# 12_I2C_schdoc.net
KiCad netlist of a schematic drawn in Altium Designer
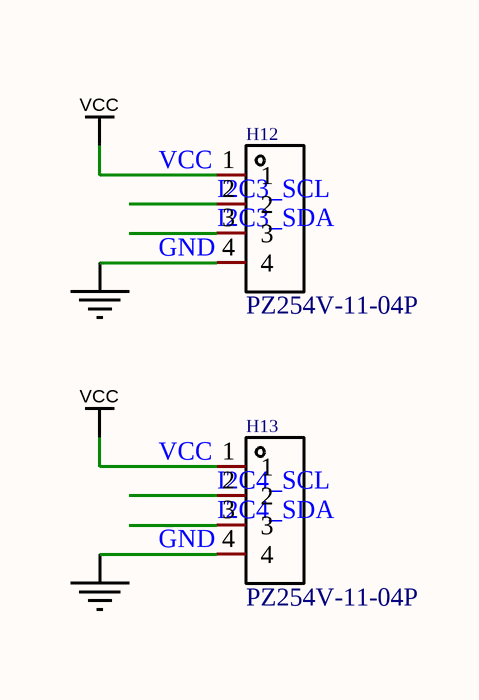
[diagram p0: 12_I2C.schdoc.schdoc]

(export (version "E")
  (design (tool "Eeschema 10.0.6"))
  (components
    (comp (ref "H12")
      (value "PZ254V-11-04P")
      (fields (field (name "NAME") "PZ254V-11-04P") (field (name "MANUFACTURER") "XFCN(兴飞)"))
      (libsource (lib "altium-import") (part "root_0_PZ254V-11-04P_"))
    )
    (comp (ref "H13")
      (value "PZ254V-11-04P")
      (fields (field (name "NAME") "PZ254V-11-04P") (field (name "MANUFACTURER") "XFCN(兴飞)"))
      (libsource (lib "altium-import") (part "root_0_PZ254V-11-04P_"))
    )
  )
  (nets
    (net (code "1") (name "/GND") (class "Default")
      (node (ref "H12") (pin "4") (pinfunction "4_4") (pintype "passive"))
      (node (ref "H13") (pin "4") (pinfunction "4_4") (pintype "passive"))
    )
    (net (code "2") (name "/I2C3_SCL") (class "Default")
      (node (ref "H12") (pin "2") (pinfunction "2_2") (pintype "passive"))
    )
    (net (code "3") (name "/I2C3_SDA") (class "Default")
      (node (ref "H12") (pin "3") (pinfunction "3_3") (pintype "passive"))
    )
    (net (code "4") (name "/I2C4_SCL") (class "Default")
      (node (ref "H13") (pin "2") (pinfunction "2_2") (pintype "passive"))
    )
    (net (code "5") (name "/I2C4_SDA") (class "Default")
      (node (ref "H13") (pin "3") (pinfunction "3_3") (pintype "passive"))
    )
    (net (code "6") (name "VCC") (class "Default")
      (node (ref "H12") (pin "1") (pinfunction "1_1") (pintype "passive"))
      (node (ref "H13") (pin "1") (pinfunction "1_1") (pintype "passive"))
    )
  )
)
